# design.net
KiCad netlist of a schematic drawn in Altium Designer
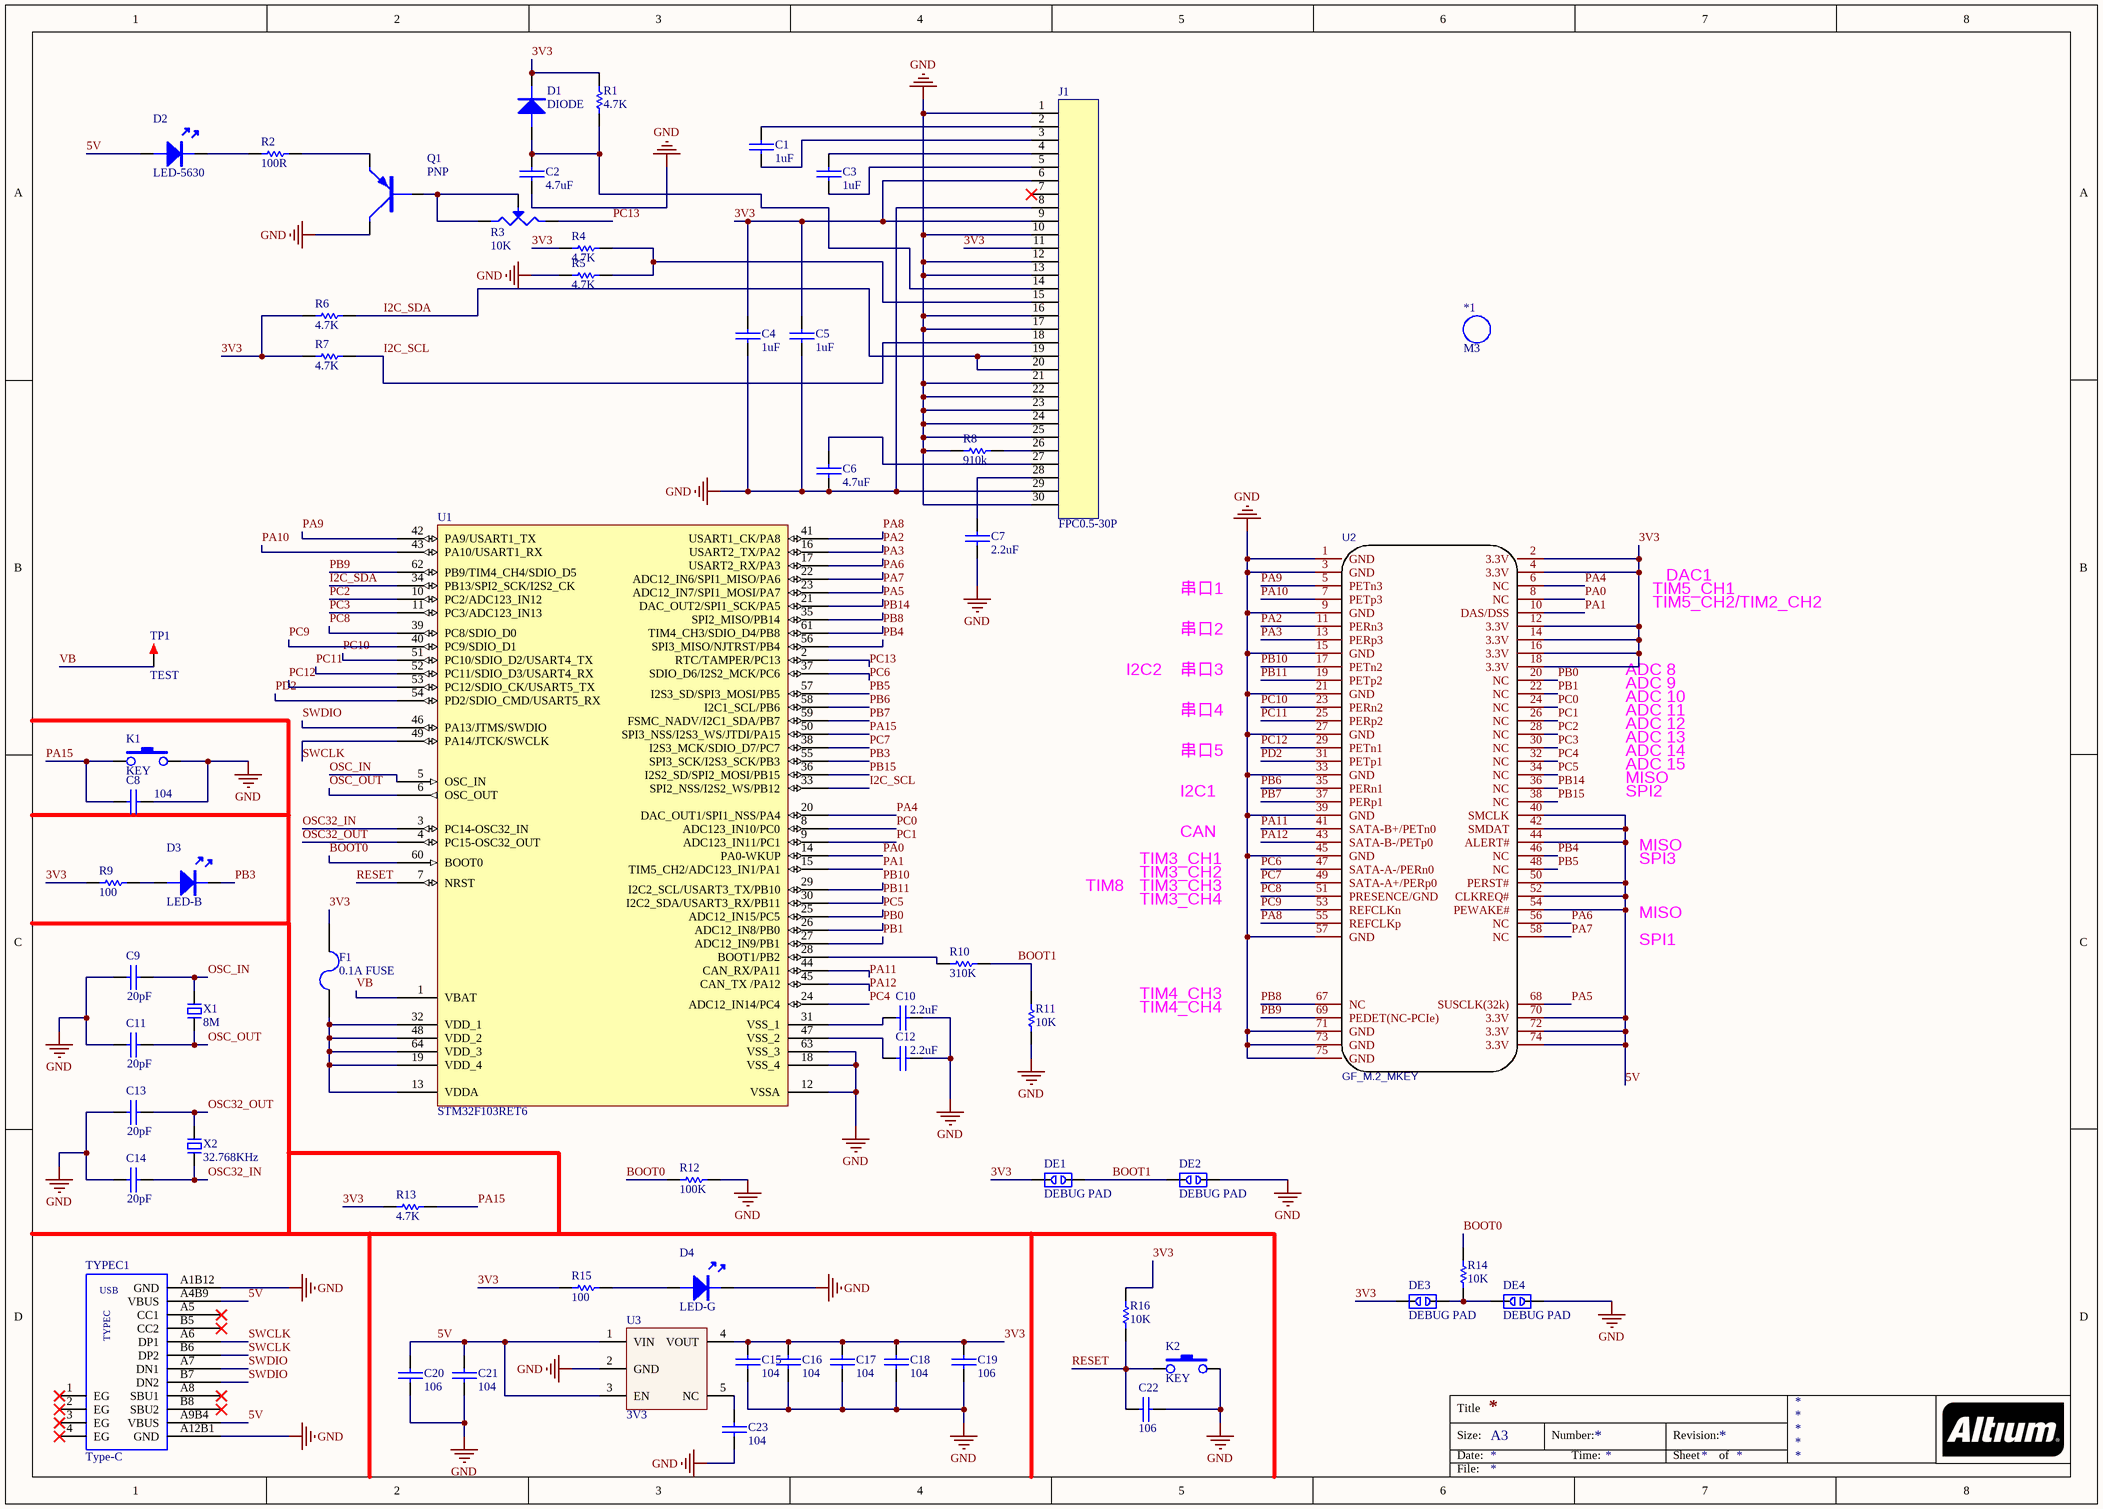
[diagram p0: 超级系统核心原理图.SchDoc]

(export (version "E")
  (design (tool "Eeschema 10.0.6"))
  (components
    (comp (ref "*1")
      (value "M3")
      (footprint "M3 140X350")
      (description "铜柱孔")
      (fields (field (name "版权归属") "源创客"))
      (libsource (lib "15.1 - 未分类器件") (part "M3"))
    )
    (comp (ref "C1")
      (value "1uF")
      (footprint "0603C")
      (description "无极性电容")
      (libsource (lib "电容") (part "CAP"))
    )
    (comp (ref "C2")
      (value "4.7uF")
      (footprint "0603C")
      (description "无极性电容")
      (libsource (lib "电容") (part "CAP"))
    )
    (comp (ref "C3")
      (value "1uF")
      (footprint "0603C")
      (description "无极性电容")
      (libsource (lib "电容") (part "CAP"))
    )
    (comp (ref "C4")
      (value "1uF")
      (footprint "0603C")
      (description "无极性电容")
      (libsource (lib "电容") (part "CAP"))
    )
    (comp (ref "C5")
      (value "1uF")
      (footprint "0603C")
      (description "无极性电容")
      (libsource (lib "电容") (part "CAP"))
    )
    (comp (ref "C6")
      (value "4.7uF")
      (footprint "0603C")
      (description "无极性电容")
      (libsource (lib "电容") (part "CAP"))
    )
    (comp (ref "C7")
      (value "2.2uF")
      (footprint "0603C")
      (description "无极性电容")
      (libsource (lib "电容") (part "CAP"))
    )
    (comp (ref "C8")
      (value "104")
      (footprint "0603C")
      (description "无极性电容")
      (libsource (lib "电容") (part "CAP"))
    )
    (comp (ref "C9")
      (value "20pF")
      (footprint "0603C")
      (description "无极性电容")
      (libsource (lib "电容") (part "CAP"))
    )
    (comp (ref "C10")
      (value "2.2uF")
      (footprint "0603C")
      (description "无极性电容")
      (libsource (lib "电容") (part "CAP"))
    )
    (comp (ref "C11")
      (value "20pF")
      (footprint "0603C")
      (description "无极性电容")
      (libsource (lib "电容") (part "CAP"))
    )
    (comp (ref "C12")
      (value "2.2uF")
      (footprint "0603C")
      (description "无极性电容")
      (libsource (lib "电容") (part "CAP"))
    )
    (comp (ref "C13")
      (value "20pF")
      (footprint "0603C")
      (description "无极性电容")
      (libsource (lib "电容") (part "CAP"))
    )
    (comp (ref "C14")
      (value "20pF")
      (footprint "0603C")
      (description "无极性电容")
      (libsource (lib "电容") (part "CAP"))
    )
    (comp (ref "C15")
      (value "104")
      (footprint "0603C")
      (description "无极性电容")
      (libsource (lib "电容") (part "CAP"))
    )
    (comp (ref "C16")
      (value "104")
      (footprint "0603C")
      (description "无极性电容")
      (libsource (lib "电容") (part "CAP"))
    )
    (comp (ref "C17")
      (value "104")
      (footprint "0603C")
      (description "无极性电容")
      (libsource (lib "电容") (part "CAP"))
    )
    (comp (ref "C18")
      (value "104")
      (footprint "0603C")
      (description "无极性电容")
      (libsource (lib "电容") (part "CAP"))
    )
    (comp (ref "C19")
      (value "106")
      (footprint "0805C")
      (description "无极性电容")
      (libsource (lib "电容") (part "CAP"))
    )
    (comp (ref "C20")
      (value "106")
      (footprint "0805C")
      (description "无极性电容")
      (libsource (lib "电容") (part "CAP"))
    )
    (comp (ref "C21")
      (value "104")
      (footprint "0603C")
      (description "无极性电容")
      (libsource (lib "电容") (part "CAP"))
    )
    (comp (ref "C22")
      (value "106")
      (footprint "0805C")
      (description "无极性电容")
      (libsource (lib "电容") (part "CAP"))
    )
    (comp (ref "C23")
      (value "104")
      (footprint "0603C")
      (description "无极性电容")
      (libsource (lib "电容") (part "CAP"))
    )
    (comp (ref "D1")
      (value "DIODE")
      (footprint "SOD-523")
      (description "普通二极管")
      (libsource (lib "二极管") (part "DIODE"))
    )
    (comp (ref "D2") (value "LED-5630") (footprint "LED-5630W") (libsource (lib "LED") (part "LED-5630")))
    (comp (ref "D3") (value "LED-B") (footprint "LED-0603B") (libsource (lib "LED") (part "LED")))
    (comp (ref "D4") (value "LED-G") (footprint "LED-0603G") (libsource (lib "LED") (part "LED")))
    (comp (ref "DE1")
      (value "DEBUG PAD")
      (footprint "DEBUG_B")
      (description "调试断点焊盘")
      (fields (field (name "版权归属") "源创客"))
      (libsource (lib "15.1 - 未分类器件") (part "DEBUG"))
    )
    (comp (ref "DE2")
      (value "DEBUG PAD")
      (footprint "DEBUG_B")
      (description "调试断点焊盘")
      (fields (field (name "版权归属") "源创客"))
      (libsource (lib "15.1 - 未分类器件") (part "DEBUG"))
    )
    (comp (ref "DE3")
      (value "DEBUG PAD")
      (footprint "DEBUG_B")
      (description "调试断点焊盘")
      (fields (field (name "版权归属") "源创客"))
      (libsource (lib "15.1 - 未分类器件") (part "DEBUG"))
    )
    (comp (ref "DE4")
      (value "DEBUG PAD")
      (footprint "DEBUG_B")
      (description "调试断点焊盘")
      (fields (field (name "版权归属") "源创客"))
      (libsource (lib "15.1 - 未分类器件") (part "DEBUG"))
    )
    (comp (ref "F1") (value "0.1A FUSE") (footprint "0805R") (libsource (lib "保险丝") (part "FUSE")))
    (comp (ref "J1")
      (value "FPC0.5-30P")
      (footprint "FPC0.5-30P")
      (description "贴片")
      (libsource (lib "FPC") (part "FPC0.5-30P"))
    )
    (comp (ref "K1") (value "KEY") (footprint "SMD-4X4X1.5") (libsource (lib "轻触开关") (part "KEY")))
    (comp (ref "K2")
      (value "KEY")
      (footprint "2X3X0.6")
      (description "薄膜按键")
      (libsource (lib "补充元件原理图库") (part "KEY"))
    )
    (comp (ref "Q1")
      (value "PNP")
      (footprint "SOT-23")
      (description "PNP三极管")
      (libsource (lib "三极管") (part "PNP"))
    )
    (comp (ref "R1") (value "4.7K") (footprint "0603R") (libsource (lib "电阻") (part "RES")))
    (comp (ref "R2") (value "100R") (footprint "0603R") (libsource (lib "电阻") (part "RES")))
    (comp (ref "R3") (value "10K") (footprint "3303W") (libsource (lib "电阻电容电感") (part "电位器2")))
    (comp (ref "R4") (value "4.7K") (footprint "0603R") (libsource (lib "电阻") (part "RES")))
    (comp (ref "R5") (value "4.7K") (footprint "0603R") (libsource (lib "电阻") (part "RES")))
    (comp (ref "R6") (value "4.7K") (footprint "0603R") (libsource (lib "电阻") (part "RES")))
    (comp (ref "R7") (value "4.7K") (footprint "0603R") (libsource (lib "电阻") (part "RES")))
    (comp (ref "R8") (value "910k") (footprint "0603R") (libsource (lib "电阻") (part "RES")))
    (comp (ref "R9") (value "100") (footprint "0603R") (libsource (lib "电阻") (part "RES")))
    (comp (ref "R10") (value "310K") (footprint "0603R") (libsource (lib "电阻") (part "RES")))
    (comp (ref "R11") (value "10K") (footprint "0603R") (libsource (lib "电阻") (part "RES")))
    (comp (ref "R12") (value "100K") (footprint "0603R") (libsource (lib "电阻") (part "RES")))
    (comp (ref "R13") (value "4.7K") (footprint "0603R") (libsource (lib "电阻") (part "RES")))
    (comp (ref "R14") (value "10K") (footprint "0603R") (libsource (lib "电阻") (part "RES")))
    (comp (ref "R15") (value "100") (footprint "0603R") (libsource (lib "电阻") (part "RES")))
    (comp (ref "R16") (value "10K") (footprint "0603R") (libsource (lib "电阻") (part "RES")))
    (comp (ref "TP1")
      (value "TEST")
      (footprint "TEST 1.4")
      (description "测试点")
      (fields (field (name "版权归属") "源创客"))
      (libsource (lib "15.1 - 未分类器件") (part "TEST"))
    )
    (comp (ref "TYPEC1")
      (value "Type-C")
      (footprint "TYPE-C")
      (description "typec 3.1半完整引脚")
      (libsource (lib "补充元件原理图库") (part "Type-C"))
    )
    (comp (ref "U1")
      (value "STM32F103RET6")
      (footprint "LQFP64 10x10_L")
      (libsource (lib "STM32系列") (part "STM32F103RET6"))
    )
    (comp (ref "U2")
      (value "GF_M.2_MKEY")
      (footprint "GF_M.2_M_KEY")
      (fields (field (name "BOM_MANUFACTURER PART") "SHOWNAME=F") (field (name "CONTRIBUTOR") "redgragon"))
      (libsource (lib "M.2 M-KEY底座与金手指") (part "GF_M.2_MKEY"))
    )
    (comp (ref "U3")
      (value "3V3")
      (footprint "HX9193")
      (description "三端稳压")
      (libsource (lib "补充元件原理图库") (part "HX9193"))
    )
    (comp (ref "X1")
      (value "8M")
      (footprint "OSC 5032-2P")
      (description "2脚无源脚晶振")
      (libsource (lib "晶振") (part "XTAL-2P"))
    )
    (comp (ref "X2")
      (value "32.768KHz")
      (footprint "OSC 3215-2P")
      (description "2脚无源脚晶振")
      (libsource (lib "晶振") (part "XTAL-2P"))
    )
  )
  (nets
    (net (code "1") (name "/3V3") (class "Default")
      (node (ref "C15") (pin "2") (pinfunction "2_2") (pintype "passive"))
      (node (ref "C16") (pin "2") (pinfunction "2_2") (pintype "passive"))
      (node (ref "C17") (pin "2") (pinfunction "2_2") (pintype "passive"))
      (node (ref "C18") (pin "2") (pinfunction "2_2") (pintype "passive"))
      (node (ref "C19") (pin "2") (pinfunction "2_2") (pintype "passive"))
      (node (ref "C4") (pin "2") (pinfunction "2_2") (pintype "passive"))
      (node (ref "C5") (pin "2") (pinfunction "2_2") (pintype "passive"))
      (node (ref "D1") (pin "K") (pinfunction "K_K") (pintype "passive"))
      (node (ref "DE1") (pin "1") (pinfunction "1_1") (pintype "passive"))
      (node (ref "DE3") (pin "1") (pinfunction "1_1") (pintype "passive"))
      (node (ref "F1") (pin "2") (pinfunction "2_2") (pintype "passive"))
      (node (ref "J1") (pin "11") (pinfunction "11_11") (pintype "passive"))
      (node (ref "J1") (pin "6") (pinfunction "6_6") (pintype "passive"))
      (node (ref "J1") (pin "9") (pinfunction "9_9") (pintype "passive"))
      (node (ref "R1") (pin "1") (pinfunction "1_1") (pintype "passive"))
      (node (ref "R13") (pin "2") (pinfunction "2_2") (pintype "passive"))
      (node (ref "R15") (pin "2") (pinfunction "2_2") (pintype "passive"))
      (node (ref "R16") (pin "2") (pinfunction "2_2") (pintype "passive"))
      (node (ref "R4") (pin "2") (pinfunction "2_2") (pintype "passive"))
      (node (ref "R6") (pin "2") (pinfunction "2_2") (pintype "passive"))
      (node (ref "R7") (pin "2") (pinfunction "2_2") (pintype "passive"))
      (node (ref "R9") (pin "2") (pinfunction "2_2") (pintype "passive"))
      (node (ref "U2") (pin "12") (pinfunction "3.3V_12") (pintype "passive"))
      (node (ref "U2") (pin "14") (pinfunction "3.3V_14") (pintype "passive"))
      (node (ref "U2") (pin "16") (pinfunction "3.3V_16") (pintype "passive"))
      (node (ref "U2") (pin "18") (pinfunction "3.3V_18") (pintype "passive"))
      (node (ref "U2") (pin "2") (pinfunction "3.3V_2") (pintype "passive"))
      (node (ref "U2") (pin "4") (pinfunction "3.3V_4") (pintype "passive"))
      (node (ref "U3") (pin "4") (pinfunction "VOUT_4") (pintype "passive"))
    )
    (net (code "2") (name "/5V") (class "Default")
      (node (ref "C20") (pin "2") (pinfunction "2_2") (pintype "passive"))
      (node (ref "C21") (pin "2") (pinfunction "2_2") (pintype "passive"))
      (node (ref "D2") (pin "A") (pinfunction "A_A") (pintype "passive"))
      (node (ref "TYPEC1") (pin "A4B9") (pinfunction "VBUS_A4B9") (pintype "passive"))
      (node (ref "TYPEC1") (pin "A9B4") (pinfunction "VBUS_A9B4") (pintype "passive"))
      (node (ref "U2") (pin "40") (pinfunction "SMCLK_40") (pintype "passive"))
      (node (ref "U2") (pin "42") (pinfunction "SMDAT_42") (pintype "passive"))
      (node (ref "U2") (pin "44") (pinfunction "ALERT#_44") (pintype "passive"))
      (node (ref "U2") (pin "50") (pinfunction "PERST#_50") (pintype "passive"))
      (node (ref "U2") (pin "52") (pinfunction "CLKREQ#_52") (pintype "passive"))
      (node (ref "U2") (pin "54") (pinfunction "PEWAKE#_54") (pintype "passive"))
      (node (ref "U2") (pin "70") (pinfunction "3.3V_70") (pintype "passive"))
      (node (ref "U2") (pin "72") (pinfunction "3.3V_72") (pintype "passive"))
      (node (ref "U2") (pin "74") (pinfunction "3.3V_74") (pintype "passive"))
      (node (ref "U3") (pin "1") (pinfunction "VIN_1") (pintype "passive"))
      (node (ref "U3") (pin "3") (pinfunction "EN_3") (pintype "passive"))
    )
    (net (code "3") (name "/BOOT0") (class "Default")
      (node (ref "R12") (pin "2") (pinfunction "2_2") (pintype "passive"))
      (node (ref "R14") (pin "1") (pinfunction "1_1") (pintype "passive"))
      (node (ref "U1") (pin "60") (pinfunction "BOOT0_60") (pintype "input"))
    )
    (net (code "4") (name "/BOOT1") (class "Default")
      (node (ref "DE1") (pin "2") (pinfunction "2_2") (pintype "passive"))
      (node (ref "DE2") (pin "1") (pinfunction "1_1") (pintype "passive"))
      (node (ref "R10") (pin "1") (pinfunction "1_1") (pintype "passive"))
      (node (ref "R11") (pin "1") (pinfunction "1_1") (pintype "passive"))
    )
    (net (code "5") (name "/I2C_SCL") (class "Default")
      (node (ref "J1") (pin "18") (pinfunction "18_18") (pintype "passive"))
      (node (ref "R7") (pin "1") (pinfunction "1_1") (pintype "passive"))
      (node (ref "U1") (pin "33") (pinfunction "SPI2_NSS/I2S2_WS/PB12_33") (pintype "bidirectional"))
    )
    (net (code "6") (name "/I2C_SDA") (class "Default")
      (node (ref "J1") (pin "19") (pinfunction "19_19") (pintype "passive"))
      (node (ref "J1") (pin "20") (pinfunction "20_20") (pintype "passive"))
      (node (ref "R6") (pin "1") (pinfunction "1_1") (pintype "passive"))
      (node (ref "U1") (pin "34") (pinfunction "PB13/SPI2_SCK/I2S2_CK_34") (pintype "bidirectional"))
    )
    (net (code "7") (name "/OSC32_IN") (class "Default")
      (node (ref "C14") (pin "2") (pinfunction "2_2") (pintype "passive"))
      (node (ref "U1") (pin "3") (pinfunction "PC14-OSC32_IN_3") (pintype "bidirectional"))
      (node (ref "X2") (pin "1") (pinfunction "1_1") (pintype "passive"))
    )
    (net (code "8") (name "/OSC32_OUT") (class "Default")
      (node (ref "C13") (pin "2") (pinfunction "2_2") (pintype "passive"))
      (node (ref "U1") (pin "4") (pinfunction "PC15-OSC32_OUT_4") (pintype "bidirectional"))
      (node (ref "X2") (pin "2") (pinfunction "2_2") (pintype "passive"))
    )
    (net (code "9") (name "/OSC_IN") (class "Default")
      (node (ref "C9") (pin "2") (pinfunction "2_2") (pintype "passive"))
      (node (ref "U1") (pin "5") (pinfunction "OSC_IN_5") (pintype "input"))
      (node (ref "X1") (pin "2") (pinfunction "2_2") (pintype "passive"))
    )
    (net (code "10") (name "/OSC_OUT") (class "Default")
      (node (ref "C11") (pin "2") (pinfunction "2_2") (pintype "passive"))
      (node (ref "U1") (pin "6") (pinfunction "OSC_OUT_6") (pintype "output"))
      (node (ref "X1") (pin "1") (pinfunction "1_1") (pintype "passive"))
    )
    (net (code "11") (name "/PA0") (class "Default")
      (node (ref "U1") (pin "14") (pinfunction "PA0-WKUP_14") (pintype "bidirectional"))
      (node (ref "U2") (pin "8") (pinfunction "NC_8") (pintype "passive"))
    )
    (net (code "12") (name "/PA1") (class "Default")
      (node (ref "U1") (pin "15") (pinfunction "TIM5_CH2/ADC123_IN1/PA1_15") (pintype "bidirectional"))
      (node (ref "U2") (pin "10") (pinfunction "DAS/DSS_10") (pintype "passive"))
    )
    (net (code "13") (name "/PA2") (class "Default")
      (node (ref "U1") (pin "16") (pinfunction "USART2_TX/PA2_16") (pintype "bidirectional"))
      (node (ref "U2") (pin "11") (pinfunction "PERn3_11") (pintype "passive"))
    )
    (net (code "14") (name "/PA3") (class "Default")
      (node (ref "U1") (pin "17") (pinfunction "USART2_RX/PA3_17") (pintype "bidirectional"))
      (node (ref "U2") (pin "13") (pinfunction "PERp3_13") (pintype "passive"))
    )
    (net (code "15") (name "/PA4") (class "Default")
      (node (ref "U1") (pin "20") (pinfunction "DAC_OUT1/SPI1_NSS/PA4_20") (pintype "bidirectional"))
      (node (ref "U2") (pin "6") (pinfunction "NC_6") (pintype "passive"))
    )
    (net (code "16") (name "/PA5") (class "Default")
      (node (ref "U1") (pin "21") (pinfunction "DAC_OUT2/SPI1_SCK/PA5_21") (pintype "bidirectional"))
      (node (ref "U2") (pin "68") (pinfunction "SUSCLK(32k)_68") (pintype "passive"))
    )
    (net (code "17") (name "/PA6") (class "Default")
      (node (ref "U1") (pin "22") (pinfunction "ADC12_IN6/SPI1_MISO/PA6_22") (pintype "bidirectional"))
      (node (ref "U2") (pin "56") (pinfunction "NC_56") (pintype "passive"))
    )
    (net (code "18") (name "/PA7") (class "Default")
      (node (ref "U1") (pin "23") (pinfunction "ADC12_IN7/SPI1_MOSI/PA7_23") (pintype "bidirectional"))
      (node (ref "U2") (pin "58") (pinfunction "NC_58") (pintype "passive"))
    )
    (net (code "19") (name "/PA8") (class "Default")
      (node (ref "U1") (pin "41") (pinfunction "USART1_CK/PA8_41") (pintype "bidirectional"))
      (node (ref "U2") (pin "55") (pinfunction "REFCLKp_55") (pintype "passive"))
    )
    (net (code "20") (name "/PA9") (class "Default")
      (node (ref "U1") (pin "42") (pinfunction "PA9/USART1_TX_42") (pintype "bidirectional"))
      (node (ref "U2") (pin "5") (pinfunction "PETn3_5") (pintype "passive"))
    )
    (net (code "21") (name "/PA10") (class "Default")
      (node (ref "U1") (pin "43") (pinfunction "PA10/USART1_RX_43") (pintype "bidirectional"))
      (node (ref "U2") (pin "7") (pinfunction "PETp3_7") (pintype "passive"))
    )
    (net (code "22") (name "/PA11") (class "Default")
      (node (ref "U1") (pin "44") (pinfunction "CAN_RX/PA11_44") (pintype "bidirectional"))
      (node (ref "U2") (pin "41") (pinfunction "SATA-B+/PETn0_41") (pintype "passive"))
    )
    (net (code "23") (name "/PA12") (class "Default")
      (node (ref "U1") (pin "45") (pinfunction "CAN_TX_/PA12_45") (pintype "bidirectional"))
      (node (ref "U2") (pin "43") (pinfunction "SATA-B-/PETp0_43") (pintype "passive"))
    )
    (net (code "24") (name "/PA15") (class "Default")
      (node (ref "C8") (pin "2") (pinfunction "2_2") (pintype "passive"))
      (node (ref "K1") (pin "1") (pinfunction "1_1") (pintype "passive"))
      (node (ref "R13") (pin "1") (pinfunction "1_1") (pintype "passive"))
      (node (ref "U1") (pin "50") (pinfunction "SPI3_NSS/I2S3_WS/JTDI/PA15_50") (pintype "bidirectional"))
    )
    (net (code "25") (name "/PB0") (class "Default")
      (node (ref "U1") (pin "26") (pinfunction "ADC12_IN8/PB0_26") (pintype "bidirectional"))
      (node (ref "U2") (pin "20") (pinfunction "NC_20") (pintype "passive"))
    )
    (net (code "26") (name "/PB1") (class "Default")
      (node (ref "U1") (pin "27") (pinfunction "ADC12_IN9/PB1_27") (pintype "bidirectional"))
      (node (ref "U2") (pin "22") (pinfunction "NC_22") (pintype "passive"))
    )
    (net (code "27") (name "/PB3") (class "Default")
      (node (ref "D3") (pin "K") (pinfunction "K_K") (pintype "passive"))
      (node (ref "U1") (pin "55") (pinfunction "SPI3_SCK/I2S3_SCK/PB3_55") (pintype "bidirectional"))
    )
    (net (code "28") (name "/PB4") (class "Default")
      (node (ref "U1") (pin "56") (pinfunction "SPI3_MISO/NJTRST/PB4_56") (pintype "bidirectional"))
      (node (ref "U2") (pin "46") (pinfunction "NC_46") (pintype "passive"))
    )
    (net (code "29") (name "/PB5") (class "Default")
      (node (ref "U1") (pin "57") (pinfunction "I2S3_SD/SPI3_MOSI/PB5_57") (pintype "bidirectional"))
      (node (ref "U2") (pin "48") (pinfunction "NC_48") (pintype "passive"))
    )
    (net (code "30") (name "/PB6") (class "Default")
      (node (ref "U1") (pin "58") (pinfunction "I2C1_SCL/PB6_58") (pintype "bidirectional"))
      (node (ref "U2") (pin "35") (pinfunction "PERn1_35") (pintype "passive"))
    )
    (net (code "31") (name "/PB7") (class "Default")
      (node (ref "U1") (pin "59") (pinfunction "FSMC_NADV/I2C1_SDA/PB7_59") (pintype "bidirectional"))
      (node (ref "U2") (pin "37") (pinfunction "PERp1_37") (pintype "passive"))
    )
    (net (code "32") (name "/PB8") (class "Default")
      (node (ref "U1") (pin "61") (pinfunction "TIM4_CH3/SDIO_D4/PB8_61") (pintype "bidirectional"))
      (node (ref "U2") (pin "67") (pinfunction "NC_67") (pintype "passive"))
    )
    (net (code "33") (name "/PB9") (class "Default")
      (node (ref "U1") (pin "62") (pinfunction "PB9/TIM4_CH4/SDIO_D5_62") (pintype "bidirectional"))
      (node (ref "U2") (pin "69") (pinfunction "PEDET(NC-PCIe)_69") (pintype "passive"))
    )
    (net (code "34") (name "/PB10") (class "Default")
      (node (ref "U1") (pin "29") (pinfunction "I2C2_SCL/USART3_TX/PB10_29") (pintype "bidirectional"))
      (node (ref "U2") (pin "17") (pinfunction "PETn2_17") (pintype "passive"))
    )
    (net (code "35") (name "/PB11") (class "Default")
      (node (ref "U1") (pin "30") (pinfunction "I2C2_SDA/USART3_RX/PB11_30") (pintype "bidirectional"))
      (node (ref "U2") (pin "19") (pinfunction "PETp2_19") (pintype "passive"))
    )
    (net (code "36") (name "/PB14") (class "Default")
      (node (ref "U1") (pin "35") (pinfunction "SPI2_MISO/PB14_35") (pintype "bidirectional"))
      (node (ref "U2") (pin "36") (pinfunction "NC_36") (pintype "passive"))
    )
    (net (code "37") (name "/PB15") (class "Default")
      (node (ref "U1") (pin "36") (pinfunction "I2S2_SD/SPI2_MOSI/PB15_36") (pintype "bidirectional"))
      (node (ref "U2") (pin "38") (pinfunction "NC_38") (pintype "passive"))
    )
    (net (code "38") (name "/PC0") (class "Default")
      (node (ref "U1") (pin "8") (pinfunction "ADC123_IN10/PC0_8") (pintype "bidirectional"))
      (node (ref "U2") (pin "24") (pinfunction "NC_24") (pintype "passive"))
    )
    (net (code "39") (name "/PC1") (class "Default")
      (node (ref "U1") (pin "9") (pinfunction "ADC123_IN11/PC1_9") (pintype "bidirectional"))
      (node (ref "U2") (pin "26") (pinfunction "NC_26") (pintype "passive"))
    )
    (net (code "40") (name "/PC2") (class "Default")
      (node (ref "U1") (pin "10") (pinfunction "PC2/ADC123_IN12_10") (pintype "bidirectional"))
      (node (ref "U2") (pin "28") (pinfunction "NC_28") (pintype "passive"))
    )
    (net (code "41") (name "/PC3") (class "Default")
      (node (ref "U1") (pin "11") (pinfunction "PC3/ADC123_IN13_11") (pintype "bidirectional"))
      (node (ref "U2") (pin "30") (pinfunction "NC_30") (pintype "passive"))
    )
    (net (code "42") (name "/PC4") (class "Default")
      (node (ref "U1") (pin "24") (pinfunction "ADC12_IN14/PC4_24") (pintype "bidirectional"))
      (node (ref "U2") (pin "32") (pinfunction "NC_32") (pintype "passive"))
    )
    (net (code "43") (name "/PC5") (class "Default")
      (node (ref "U1") (pin "25") (pinfunction "ADC12_IN15/PC5_25") (pintype "bidirectional"))
      (node (ref "U2") (pin "34") (pinfunction "NC_34") (pintype "passive"))
    )
    (net (code "44") (name "/PC6") (class "Default")
      (node (ref "U1") (pin "37") (pinfunction "SDIO_D6/I2S2_MCK/PC6_37") (pintype "bidirectional"))
      (node (ref "U2") (pin "47") (pinfunction "SATA-A-/PERn0_47") (pintype "passive"))
    )
    (net (code "45") (name "/PC7") (class "Default")
      (node (ref "U1") (pin "38") (pinfunction "I2S3_MCK/SDIO_D7/PC7_38") (pintype "bidirectional"))
      (node (ref "U2") (pin "49") (pinfunction "SATA-A+/PERp0_49") (pintype "passive"))
    )
    (net (code "46") (name "/PC8") (class "Default")
      (node (ref "U1") (pin "39") (pinfunction "PC8/SDIO_D0_39") (pintype "bidirectional"))
      (node (ref "U2") (pin "51") (pinfunction "PRESENCE/GND_51") (pintype "passive"))
    )
    (net (code "47") (name "/PC9") (class "Default")
      (node (ref "U1") (pin "40") (pinfunction "PC9/SDIO_D1_40") (pintype "bidirectional"))
      (node (ref "U2") (pin "53") (pinfunction "REFCLKn_53") (pintype "passive"))
    )
    (net (code "48") (name "/PC10") (class "Default")
      (node (ref "U1") (pin "51") (pinfunction "PC10/SDIO_D2/USART4_TX_51") (pintype "bidirectional"))
      (node (ref "U2") (pin "23") (pinfunction "PERn2_23") (pintype "passive"))
    )
    (net (code "49") (name "/PC11") (class "Default")
      (node (ref "U1") (pin "52") (pinfunction "PC11/SDIO_D3/USART4_RX_52") (pintype "bidirectional"))
      (node (ref "U2") (pin "25") (pinfunction "PERp2_25") (pintype "passive"))
    )
    (net (code "50") (name "/PC12") (class "Default")
      (node (ref "U1") (pin "53") (pinfunction "PC12/SDIO_CK/USART5_TX_53") (pintype "bidirectional"))
      (node (ref "U2") (pin "29") (pinfunction "PETn1_29") (pintype "passive"))
    )
    (net (code "51") (name "/PC13") (class "Default")
      (node (ref "R3") (pin "2") (pinfunction "2_2") (pintype "passive"))
      (node (ref "U1") (pin "2") (pinfunction "RTC/TAMPER/PC13_2") (pintype "bidirectional"))
    )
    (net (code "52") (name "/PD2") (class "Default")
      (node (ref "U1") (pin "54") (pinfunction "PD2/SDIO_CMD/USART5_RX_54") (pintype "bidirectional"))
      (node (ref "U2") (pin "31") (pinfunction "PETp1_31") (pintype "passive"))
    )
    (net (code "53") (name "/RESET") (class "Default")
      (node (ref "C22") (pin "2") (pinfunction "2_2") (pintype "passive"))
      (node (ref "K2") (pin "1") (pinfunction "1_1") (pintype "passive"))
      (node (ref "R16") (pin "1") (pinfunction "1_1") (pintype "passive"))
      (node (ref "U1") (pin "7") (pinfunction "NRST_7") (pintype "bidirectional"))
    )
    (net (code "54") (name "/SWCLK") (class "Default")
      (node (ref "TYPEC1") (pin "A6") (pinfunction "DP1_A6") (pintype "passive"))
      (node (ref "TYPEC1") (pin "B6") (pinfunction "DP2_B6") (pintype "passive"))
      (node (ref "U1") (pin "49") (pinfunction "PA14/JTCK/SWCLK_49") (pintype "bidirectional"))
    )
    (net (code "55") (name "/SWDIO") (class "Default")
      (node (ref "TYPEC1") (pin "A7") (pinfunction "DN1_A7") (pintype "passive"))
      (node (ref "TYPEC1") (pin "B7") (pinfunction "DN2_B7") (pintype "passive"))
      (node (ref "U1") (pin "46") (pinfunction "PA13/JTMS/SWDIO_46") (pintype "bidirectional"))
    )
    (net (code "56") (name "/VB") (class "Default")
      (node (ref "TP1") (pin "1") (pinfunction "1_1") (pintype "passive"))
      (node (ref "U1") (pin "1") (pinfunction "VBAT_1") (pintype "power_in"))
    )
    (net (code "57") (name "GND") (class "Default")
      (node (ref "C10") (pin "2") (pinfunction "2_2") (pintype "passive"))
      (node (ref "C11") (pin "1") (pinfunction "1_1") (pintype "passive"))
      (node (ref "C12") (pin "2") (pinfunction "2_2") (pintype "passive"))
      (node (ref "C13") (pin "1") (pinfunction "1_1") (pintype "passive"))
      (node (ref "C14") (pin "1") (pinfunction "1_1") (pintype "passive"))
      (node (ref "C15") (pin "1") (pinfunction "1_1") (pintype "passive"))
      (node (ref "C16") (pin "1") (pinfunction "1_1") (pintype "passive"))
      (node (ref "C17") (pin "1") (pinfunction "1_1") (pintype "passive"))
      (node (ref "C18") (pin "1") (pinfunction "1_1") (pintype "passive"))
      (node (ref "C19") (pin "1") (pinfunction "1_1") (pintype "passive"))
      (node (ref "C2") (pin "1") (pinfunction "1_1") (pintype "passive"))
      (node (ref "C20") (pin "1") (pinfunction "1_1") (pintype "passive"))
      (node (ref "C21") (pin "1") (pinfunction "1_1") (pintype "passive"))
      (node (ref "C22") (pin "1") (pinfunction "1_1") (pintype "passive"))
      (node (ref "C23") (pin "1") (pinfunction "1_1") (pintype "passive"))
      (node (ref "C4") (pin "1") (pinfunction "1_1") (pintype "passive"))
      (node (ref "C5") (pin "1") (pinfunction "1_1") (pintype "passive"))
      (node (ref "C6") (pin "1") (pinfunction "1_1") (pintype "passive"))
      (node (ref "C7") (pin "1") (pinfunction "1_1") (pintype "passive"))
      (node (ref "C8") (pin "1") (pinfunction "1_1") (pintype "passive"))
      (node (ref "C9") (pin "1") (pinfunction "1_1") (pintype "passive"))
      (node (ref "D4") (pin "K") (pinfunction "K_K") (pintype "passive"))
      (node (ref "DE2") (pin "2") (pinfunction "2_2") (pintype "passive"))
      (node (ref "DE4") (pin "2") (pinfunction "2_2") (pintype "passive"))
      (node (ref "J1") (pin "1") (pinfunction "1_1") (pintype "passive"))
      (node (ref "J1") (pin "10") (pinfunction "10_10") (pintype "passive"))
      (node (ref "J1") (pin "12") (pinfunction "12_12") (pintype "passive"))
      (node (ref "J1") (pin "13") (pinfunction "13_13") (pintype "passive"))
      (node (ref "J1") (pin "16") (pinfunction "16_16") (pintype "passive"))
      (node (ref "J1") (pin "17") (pinfunction "17_17") (pintype "passive"))
      (node (ref "J1") (pin "21") (pinfunction "21_21") (pintype "passive"))
      (node (ref "J1") (pin "22") (pinfunction "22_22") (pintype "passive"))
      (node (ref "J1") (pin "23") (pinfunction "23_23") (pintype "passive"))
      (node (ref "J1") (pin "24") (pinfunction "24_24") (pintype "passive"))
      (node (ref "J1") (pin "25") (pinfunction "25_25") (pintype "passive"))
      (node (ref "J1") (pin "29") (pinfunction "29_29") (pintype "passive"))
      (node (ref "J1") (pin "30") (pinfunction "30_30") (pintype "passive"))
      (node (ref "J1") (pin "8") (pinfunction "8_8") (pintype "passive"))
      (node (ref "K1") (pin "3") (pinfunction "3_3") (pintype "passive"))
      (node (ref "K2") (pin "3") (pinfunction "3_3") (pintype "passive"))
      (node (ref "Q1") (pin "C") (pinfunction "C_C") (pintype "passive"))
      (node (ref "R11") (pin "2") (pinfunction "2_2") (pintype "passive"))
      (node (ref "R12") (pin "1") (pinfunction "1_1") (pintype "passive"))
      (node (ref "R5") (pin "2") (pinfunction "2_2") (pintype "passive"))
      (node (ref "R8") (pin "2") (pinfunction "2_2") (pintype "passive"))
      (node (ref "TYPEC1") (pin "A12B1") (pinfunction "GND_A12B1") (pintype "passive"))
      (node (ref "TYPEC1") (pin "A1B12") (pinfunction "GND_A1B12") (pintype "passive"))
      (node (ref "U1") (pin "12") (pinfunction "VSSA_12") (pintype "power_in"))
      (node (ref "U1") (pin "18") (pinfunction "VSS_4_18") (pintype "power_in"))
      (node (ref "U1") (pin "63") (pinfunction "VSS_3_63") (pintype "power_in"))
      (node (ref "U2") (pin "1") (pinfunction "GND_1") (pintype "passive"))
      (node (ref "U2") (pin "15") (pinfunction "GND_15") (pintype "passive"))
      (node (ref "U2") (pin "21") (pinfunction "GND_21") (pintype "passive"))
      (node (ref "U2") (pin "27") (pinfunction "GND_27") (pintype "passive"))
      (node (ref "U2") (pin "3") (pinfunction "GND_3") (pintype "passive"))
      (node (ref "U2") (pin "33") (pinfunction "GND_33") (pintype "passive"))
      (node (ref "U2") (pin "39") (pinfunction "GND_39") (pintype "passive"))
      (node (ref "U2") (pin "45") (pinfunction "GND_45") (pintype "passive"))
      (node (ref "U2") (pin "57") (pinfunction "GND_57") (pintype "passive"))
      (node (ref "U2") (pin "71") (pinfunction "GND_71") (pintype "passive"))
      (node (ref "U2") (pin "73") (pinfunction "GND_73") (pintype "passive"))
      (node (ref "U2") (pin "75") (pinfunction "GND_75") (pintype "passive"))
      (node (ref "U2") (pin "9") (pinfunction "GND_9") (pintype "passive"))
      (node (ref "U3") (pin "2") (pinfunction "GND_2") (pintype "passive"))
    )
    (net (code "58") (name "Net-(C1-Pad1)") (class "Default")
      (node (ref "C1") (pin "1") (pinfunction "1_1") (pintype "passive"))
      (node (ref "J1") (pin "3") (pinfunction "3_3") (pintype "passive"))
    )
    (net (code "59") (name "Net-(C1-Pad2)") (class "Default")
      (node (ref "C1") (pin "2") (pinfunction "2_2") (pintype "passive"))
      (node (ref "J1") (pin "2") (pinfunction "2_2") (pintype "passive"))
    )
    (net (code "60") (name "Net-(C2-Pad2)") (class "Default")
      (node (ref "C2") (pin "2") (pinfunction "2_2") (pintype "passive"))
      (node (ref "D1") (pin "A") (pinfunction "A_A") (pintype "passive"))
      (node (ref "J1") (pin "14") (pinfunction "14_14") (pintype "passive"))
      (node (ref "R1") (pin "2") (pinfunction "2_2") (pintype "passive"))
    )
    (net (code "61") (name "Net-(C3-Pad1)") (class "Default")
      (node (ref "C3") (pin "1") (pinfunction "1_1") (pintype "passive"))
      (node (ref "J1") (pin "5") (pinfunction "5_5") (pintype "passive"))
    )
    (net (code "62") (name "Net-(C3-Pad2)") (class "Default")
      (node (ref "C3") (pin "2") (pinfunction "2_2") (pintype "passive"))
      (node (ref "J1") (pin "4") (pinfunction "4_4") (pintype "passive"))
    )
    (net (code "63") (name "Net-(C6-Pad2)") (class "Default")
      (node (ref "C6") (pin "2") (pinfunction "2_2") (pintype "passive"))
      (node (ref "J1") (pin "27") (pinfunction "27_27") (pintype "passive"))
    )
    (net (code "64") (name "Net-(C7-Pad2)") (class "Default")
      (node (ref "C7") (pin "2") (pinfunction "2_2") (pintype "passive"))
      (node (ref "J1") (pin "28") (pinfunction "28_28") (pintype "passive"))
    )
    (net (code "65") (name "Net-(D2-PadK)") (class "Default")
      (node (ref "D2") (pin "K") (pinfunction "K_K") (pintype "passive"))
      (node (ref "R2") (pin "1") (pinfunction "1_1") (pintype "passive"))
    )
    (net (code "66") (name "Net-(D3-PadA)") (class "Default")
      (node (ref "D3") (pin "A") (pinfunction "A_A") (pintype "passive"))
      (node (ref "R9") (pin "1") (pinfunction "1_1") (pintype "passive"))
    )
    (net (code "67") (name "Net-(D4-PadA)") (class "Default")
      (node (ref "D4") (pin "A") (pinfunction "A_A") (pintype "passive"))
      (node (ref "R15") (pin "1") (pinfunction "1_1") (pintype "passive"))
    )
    (net (code "68") (name "Net-(DE3-Pad2)") (class "Default")
      (node (ref "DE3") (pin "2") (pinfunction "2_2") (pintype "passive"))
      (node (ref "DE4") (pin "1") (pinfunction "1_1") (pintype "passive"))
      (node (ref "R14") (pin "2") (pinfunction "2_2") (pintype "passive"))
    )
    (net (code "69") (name "Net-(J1-Pad15)") (class "Default")
      (node (ref "J1") (pin "15") (pinfunction "15_15") (pintype "passive"))
      (node (ref "R4") (pin "1") (pinfunction "1_1") (pintype "passive"))
      (node (ref "R5") (pin "1") (pinfunction "1_1") (pintype "passive"))
    )
    (net (code "70") (name "Net-(J1-Pad26)") (class "Default")
      (node (ref "J1") (pin "26") (pinfunction "26_26") (pintype "passive"))
      (node (ref "R8") (pin "1") (pinfunction "1_1") (pintype "passive"))
    )
    (net (code "71") (name "Net-(Q1-PadE)") (class "Default")
      (node (ref "Q1") (pin "E") (pinfunction "E_E") (pintype "passive"))
      (node (ref "R2") (pin "2") (pinfunction "2_2") (pintype "passive"))
    )
    (net (code "72") (name "Net-(R3-W)") (class "Default")
      (node (ref "Q1") (pin "B") (pinfunction "B_B") (pintype "passive"))
      (node (ref "R3") (pin "1") (pinfunction "1_1") (pintype "passive"))
      (node (ref "R3") (pin "3") (pinfunction "W_3") (pintype "passive"))
    )
    (net (code "73") (name "Net-(U1-BOOT1{slash}PB2)") (class "Default")
      (node (ref "R10") (pin "2") (pinfunction "2_2") (pintype "passive"))
      (node (ref "U1") (pin "28") (pinfunction "BOOT1/PB2_28") (pintype "bidirectional"))
    )
    (net (code "74") (name "Net-(U1-VDDA)") (class "Default")
      (node (ref "F1") (pin "1") (pinfunction "1_1") (pintype "passive"))
      (node (ref "U1") (pin "13") (pinfunction "VDDA_13") (pintype "power_in"))
      (node (ref "U1") (pin "19") (pinfunction "VDD_4_19") (pintype "power_in"))
      (node (ref "U1") (pin "32") (pinfunction "VDD_1_32") (pintype "power_in"))
      (node (ref "U1") (pin "48") (pinfunction "VDD_2_48") (pintype "power_in"))
      (node (ref "U1") (pin "64") (pinfunction "VDD_3_64") (pintype "power_in"))
    )
    (net (code "75") (name "Net-(U1-VSS_1)") (class "Default")
      (node (ref "C10") (pin "1") (pinfunction "1_1") (pintype "passive"))
      (node (ref "U1") (pin "31") (pinfunction "VSS_1_31") (pintype "passive"))
    )
    (net (code "76") (name "Net-(U1-VSS_2)") (class "Default")
      (node (ref "C12") (pin "1") (pinfunction "1_1") (pintype "passive"))
      (node (ref "U1") (pin "47") (pinfunction "VSS_2_47") (pintype "passive"))
    )
    (net (code "77") (name "Net-(U3-NC)") (class "Default")
      (node (ref "C23") (pin "2") (pinfunction "2_2") (pintype "passive"))
      (node (ref "U3") (pin "5") (pinfunction "NC_5") (pintype "passive"))
    )
    (net (code "78") (name "unconnected-(J1-Pad7)") (class "Default")
      (node (ref "J1") (pin "7") (pinfunction "7_7") (pintype "passive+no_connect"))
    )
    (net (code "79") (name "unconnected-(TYPEC1-CC1-PadA5)") (class "Default")
      (node (ref "TYPEC1") (pin "A5") (pinfunction "CC1_A5") (pintype "passive+no_connect"))
    )
    (net (code "80") (name "unconnected-(TYPEC1-CC2-PadB5)") (class "Default")
      (node (ref "TYPEC1") (pin "B5") (pinfunction "CC2_B5") (pintype "passive+no_connect"))
    )
    (net (code "81") (name "unconnected-(TYPEC1-EG-Pad1)") (class "Default")
      (node (ref "TYPEC1") (pin "1") (pinfunction "EG_1") (pintype "passive+no_connect"))
    )
    (net (code "82") (name "unconnected-(TYPEC1-EG-Pad2)") (class "Default")
      (node (ref "TYPEC1") (pin "2") (pinfunction "EG_2") (pintype "passive+no_connect"))
    )
    (net (code "83") (name "unconnected-(TYPEC1-EG-Pad3)") (class "Default")
      (node (ref "TYPEC1") (pin "3") (pinfunction "EG_3") (pintype "passive+no_connect"))
    )
    (net (code "84") (name "unconnected-(TYPEC1-EG-Pad4)") (class "Default")
      (node (ref "TYPEC1") (pin "4") (pinfunction "EG_4") (pintype "passive+no_connect"))
    )
    (net (code "85") (name "unconnected-(TYPEC1-SBU1-PadA8)") (class "Default")
      (node (ref "TYPEC1") (pin "A8") (pinfunction "SBU1_A8") (pintype "passive+no_connect"))
    )
    (net (code "86") (name "unconnected-(TYPEC1-SBU2-PadB8)") (class "Default")
      (node (ref "TYPEC1") (pin "B8") (pinfunction "SBU2_B8") (pintype "passive+no_connect"))
    )
  )
)
